# waterduck.net
KiCad netlist of a schematic drawn in EAGLE
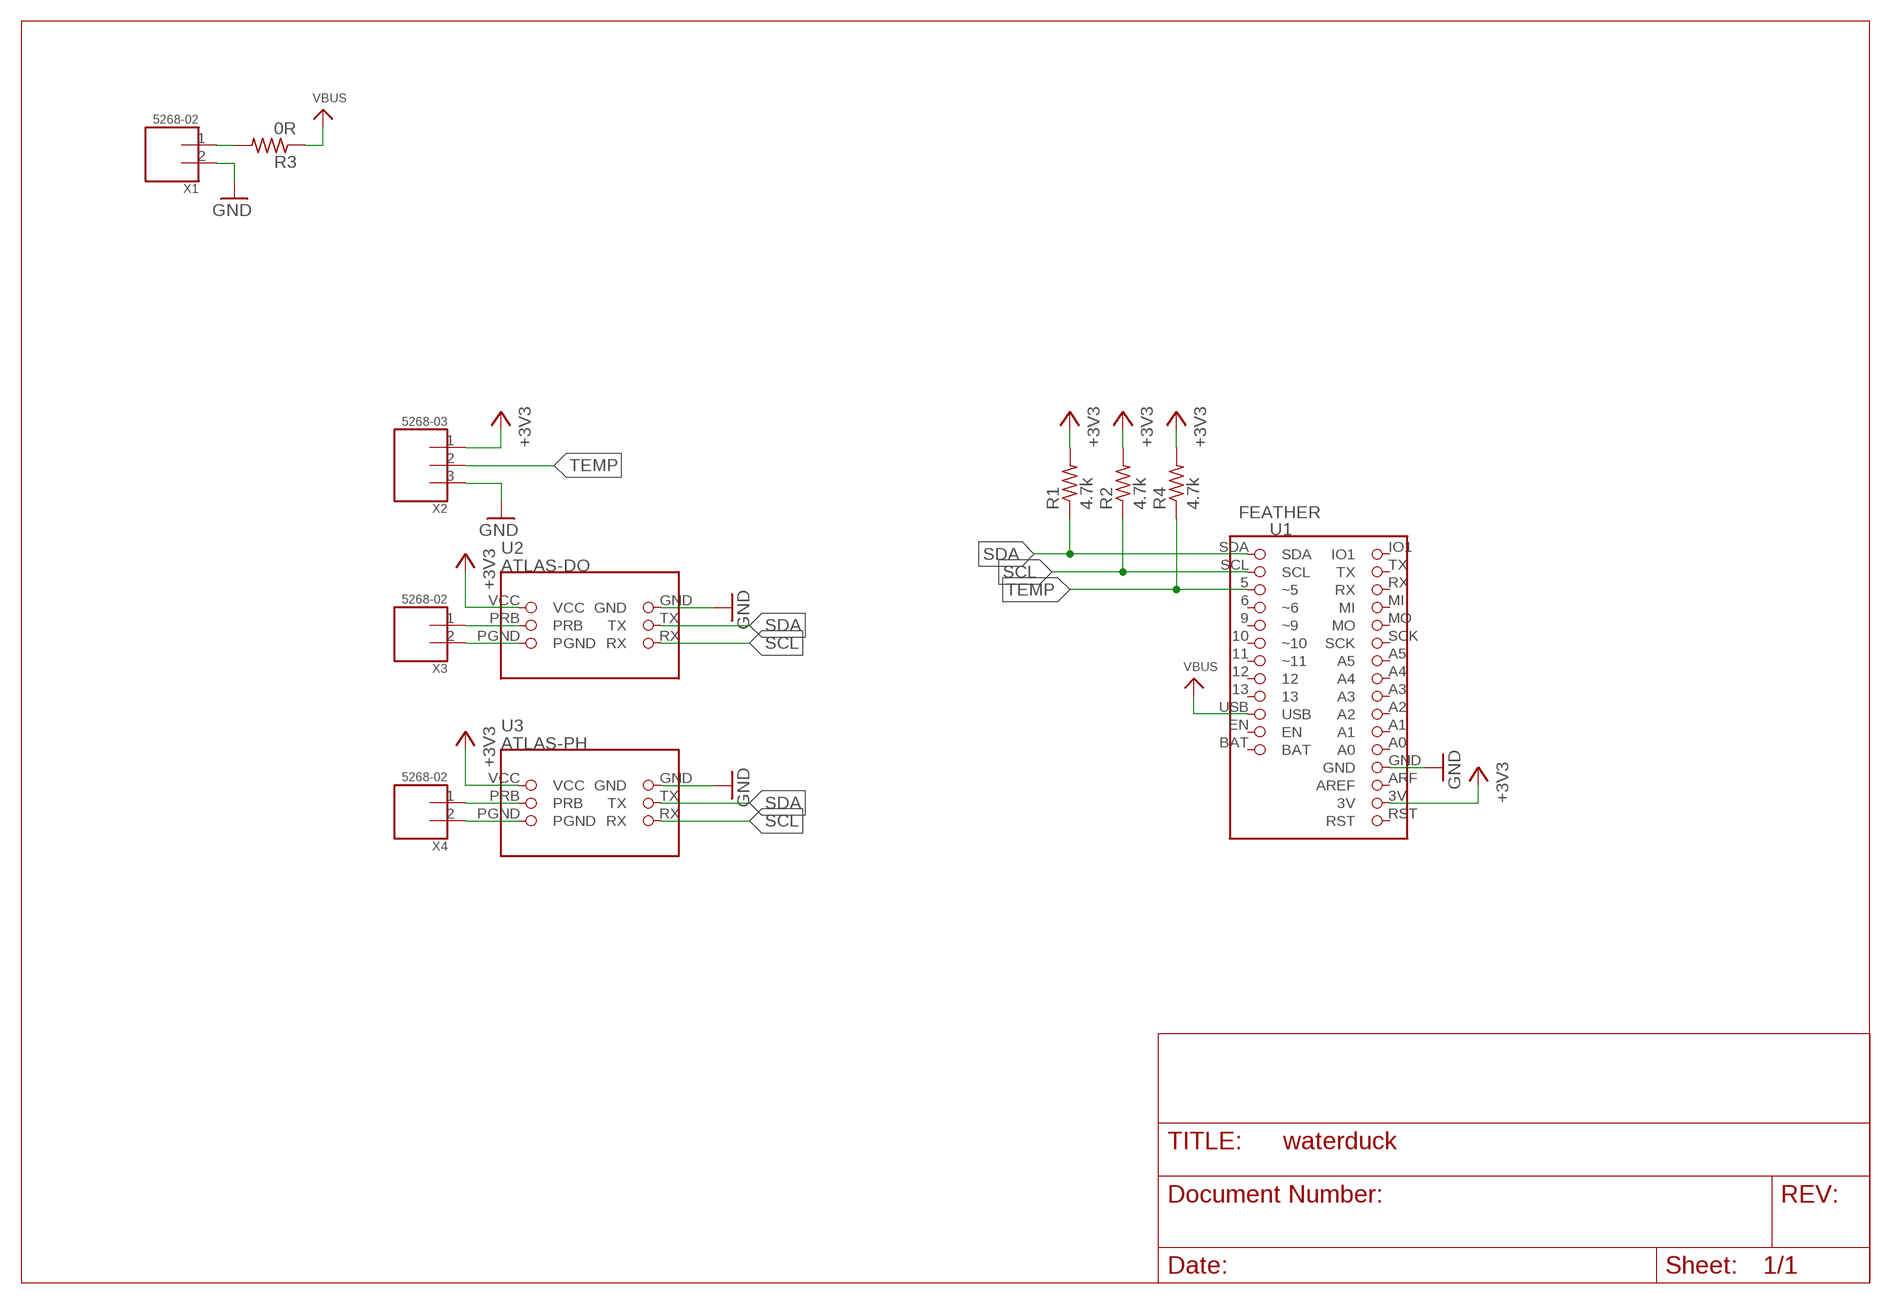
[diagram p0: schematic, sheet 1]

(export (version "E")
  (design (tool "Eeschema 10.0.6"))
  (components
    (comp (ref "R1")
      (value "4.7k")
      (footprint "eagle-import:R0603(1608)")
      (libsource (lib "eagle-import") (part "R0603(1608)"))
    )
    (comp (ref "R2")
      (value "4.7k")
      (footprint "eagle-import:R0603(1608)")
      (libsource (lib "eagle-import") (part "R0603(1608)"))
    )
    (comp (ref "R3")
      (value "0R")
      (footprint "eagle-import:R0603(1608)")
      (libsource (lib "eagle-import") (part "R0603(1608)"))
    )
    (comp (ref "R4")
      (value "4.7k")
      (footprint "eagle-import:R0603(1608)")
      (libsource (lib "eagle-import") (part "R0603(1608)"))
    )
    (comp (ref "U1")
      (value "FEATHER")
      (footprint "eagle-import:FEATHER")
      (libsource (lib "eagle-import") (part "FEATHER"))
    )
    (comp (ref "U2")
      (value "ATLAS-DO")
      (footprint "eagle-import:ATLAS")
      (libsource (lib "eagle-import") (part "ATLAS-DO"))
    )
    (comp (ref "U3")
      (value "ATLAS-PH")
      (footprint "eagle-import:ATLAS")
      (libsource (lib "eagle-import") (part "ATLAS-PH"))
    )
    (comp (ref "X1")
      (value "5268-02")
      (footprint "eagle-import:5628-02")
      (libsource (lib "eagle-import") (part "5268-02"))
    )
    (comp (ref "X2")
      (value "5268-03")
      (footprint "eagle-import:5268-03")
      (libsource (lib "eagle-import") (part "5268-03"))
    )
    (comp (ref "X3")
      (value "5268-02")
      (footprint "eagle-import:5628-02")
      (libsource (lib "eagle-import") (part "5268-02"))
    )
    (comp (ref "X4")
      (value "5268-02")
      (footprint "eagle-import:5628-02")
      (libsource (lib "eagle-import") (part "5268-02"))
    )
  )
  (nets
    (net (code "1") (name "+3V3") (class "Default")
      (node (ref "R1") (pin "2") (pinfunction "2_2") (pintype "passive"))
      (node (ref "R2") (pin "2") (pinfunction "2_2") (pintype "passive"))
      (node (ref "R4") (pin "2") (pinfunction "2_2") (pintype "passive"))
      (node (ref "U1") (pin "3V") (pinfunction "3V_3V") (pintype "passive"))
      (node (ref "U2") (pin "VCC") (pinfunction "VCC_VCC") (pintype "passive"))
      (node (ref "U3") (pin "VCC") (pinfunction "VCC_VCC") (pintype "passive"))
      (node (ref "X2") (pin "1") (pinfunction "1_1") (pintype "bidirectional"))
    )
    (net (code "2") (name "GND") (class "Default")
      (node (ref "U1") (pin "GND") (pinfunction "GND_GND") (pintype "passive"))
      (node (ref "U2") (pin "GND") (pinfunction "GND_GND") (pintype "passive"))
      (node (ref "U3") (pin "GND") (pinfunction "GND_GND") (pintype "passive"))
      (node (ref "X1") (pin "2") (pinfunction "2_2") (pintype "bidirectional"))
      (node (ref "X2") (pin "3") (pinfunction "3_3") (pintype "bidirectional"))
    )
    (net (code "3") (name "Net-(R3-Pad2)") (class "Default")
      (node (ref "R3") (pin "2") (pinfunction "2_2") (pintype "passive"))
      (node (ref "X1") (pin "1") (pinfunction "1_1") (pintype "bidirectional"))
    )
    (net (code "4") (name "Net-(U2-PadPGND)") (class "Default")
      (node (ref "U2") (pin "PGND") (pinfunction "PGND_PGND") (pintype "passive"))
      (node (ref "X3") (pin "2") (pinfunction "2_2") (pintype "bidirectional"))
    )
    (net (code "5") (name "Net-(U2-PadPRB)") (class "Default")
      (node (ref "U2") (pin "PRB") (pinfunction "PRB_PRB") (pintype "passive"))
      (node (ref "X3") (pin "1") (pinfunction "1_1") (pintype "bidirectional"))
    )
    (net (code "6") (name "Net-(U3-PadPGND)") (class "Default")
      (node (ref "U3") (pin "PGND") (pinfunction "PGND_PGND") (pintype "passive"))
      (node (ref "X4") (pin "2") (pinfunction "2_2") (pintype "bidirectional"))
    )
    (net (code "7") (name "Net-(U3-PadPRB)") (class "Default")
      (node (ref "U3") (pin "PRB") (pinfunction "PRB_PRB") (pintype "passive"))
      (node (ref "X4") (pin "1") (pinfunction "1_1") (pintype "bidirectional"))
    )
    (net (code "8") (name "SCL") (class "Default")
      (node (ref "R2") (pin "1") (pinfunction "1_1") (pintype "passive"))
      (node (ref "U1") (pin "SCL") (pinfunction "SCL_SCL") (pintype "passive"))
      (node (ref "U2") (pin "RX") (pinfunction "RX_RX") (pintype "passive"))
      (node (ref "U3") (pin "RX") (pinfunction "RX_RX") (pintype "passive"))
    )
    (net (code "9") (name "SDA") (class "Default")
      (node (ref "R1") (pin "1") (pinfunction "1_1") (pintype "passive"))
      (node (ref "U1") (pin "SDA") (pinfunction "SDA_SDA") (pintype "passive"))
      (node (ref "U2") (pin "TX") (pinfunction "TX_TX") (pintype "passive"))
      (node (ref "U3") (pin "TX") (pinfunction "TX_TX") (pintype "passive"))
    )
    (net (code "10") (name "TEMP") (class "Default")
      (node (ref "R4") (pin "1") (pinfunction "1_1") (pintype "passive"))
      (node (ref "U1") (pin "5") (pinfunction "~{5}_5") (pintype "passive"))
      (node (ref "X2") (pin "2") (pinfunction "2_2") (pintype "bidirectional"))
    )
    (net (code "11") (name "VBUS") (class "Default")
      (node (ref "R3") (pin "1") (pinfunction "1_1") (pintype "passive"))
      (node (ref "U1") (pin "USB") (pinfunction "USB_USB") (pintype "passive"))
    )
    (net (code "12") (name "unconnected-(U1-AREF-PadARF)") (class "Default")
      (node (ref "U1") (pin "ARF") (pinfunction "AREF_ARF") (pintype "passive"))
    )
    (net (code "13") (name "unconnected-(U1-Pad12)") (class "Default")
      (node (ref "U1") (pin "12") (pinfunction "12_12") (pintype "passive"))
    )
    (net (code "14") (name "unconnected-(U1-Pad13)") (class "Default")
      (node (ref "U1") (pin "13") (pinfunction "13_13") (pintype "passive"))
    )
    (net (code "15") (name "unconnected-(U1-PadA0)") (class "Default")
      (node (ref "U1") (pin "A0") (pinfunction "A0_A0") (pintype "passive"))
    )
    (net (code "16") (name "unconnected-(U1-PadA1)") (class "Default")
      (node (ref "U1") (pin "A1") (pinfunction "A1_A1") (pintype "passive"))
    )
    (net (code "17") (name "unconnected-(U1-PadA2)") (class "Default")
      (node (ref "U1") (pin "A2") (pinfunction "A2_A2") (pintype "passive"))
    )
    (net (code "18") (name "unconnected-(U1-PadA3)") (class "Default")
      (node (ref "U1") (pin "A3") (pinfunction "A3_A3") (pintype "passive"))
    )
    (net (code "19") (name "unconnected-(U1-PadA4)") (class "Default")
      (node (ref "U1") (pin "A4") (pinfunction "A4_A4") (pintype "passive"))
    )
    (net (code "20") (name "unconnected-(U1-PadA5)") (class "Default")
      (node (ref "U1") (pin "A5") (pinfunction "A5_A5") (pintype "passive"))
    )
    (net (code "21") (name "unconnected-(U1-PadBAT)") (class "Default")
      (node (ref "U1") (pin "BAT") (pinfunction "BAT_BAT") (pintype "passive"))
    )
    (net (code "22") (name "unconnected-(U1-PadEN)") (class "Default")
      (node (ref "U1") (pin "EN") (pinfunction "EN_EN") (pintype "passive"))
    )
    (net (code "23") (name "unconnected-(U1-PadIO1)") (class "Default")
      (node (ref "U1") (pin "IO1") (pinfunction "IO1_IO1") (pintype "passive"))
    )
    (net (code "24") (name "unconnected-(U1-PadMI)") (class "Default")
      (node (ref "U1") (pin "MI") (pinfunction "MI_MI") (pintype "passive"))
    )
    (net (code "25") (name "unconnected-(U1-PadMO)") (class "Default")
      (node (ref "U1") (pin "MO") (pinfunction "MO_MO") (pintype "passive"))
    )
    (net (code "26") (name "unconnected-(U1-PadRST)") (class "Default")
      (node (ref "U1") (pin "RST") (pinfunction "RST_RST") (pintype "passive"))
    )
    (net (code "27") (name "unconnected-(U1-PadRX)") (class "Default")
      (node (ref "U1") (pin "RX") (pinfunction "RX_RX") (pintype "passive"))
    )
    (net (code "28") (name "unconnected-(U1-PadSCK)") (class "Default")
      (node (ref "U1") (pin "SCK") (pinfunction "SCK_SCK") (pintype "passive"))
    )
    (net (code "29") (name "unconnected-(U1-PadTX)") (class "Default")
      (node (ref "U1") (pin "TX") (pinfunction "TX_TX") (pintype "passive"))
    )
    (net (code "30") (name "unconnected-(U1-~{6}-Pad6)") (class "Default")
      (node (ref "U1") (pin "6") (pinfunction "~{6}_6") (pintype "passive"))
    )
    (net (code "31") (name "unconnected-(U1-~{9}-Pad9)") (class "Default")
      (node (ref "U1") (pin "9") (pinfunction "~{9}_9") (pintype "passive"))
    )
    (net (code "32") (name "unconnected-(U1-~{10}-Pad10)") (class "Default")
      (node (ref "U1") (pin "10") (pinfunction "~{10}_10") (pintype "passive"))
    )
    (net (code "33") (name "unconnected-(U1-~{11}-Pad11)") (class "Default")
      (node (ref "U1") (pin "11") (pinfunction "~{11}_11") (pintype "passive"))
    )
  )
)
